# Ver_5.net
KiCad netlist of a schematic drawn in EAGLE
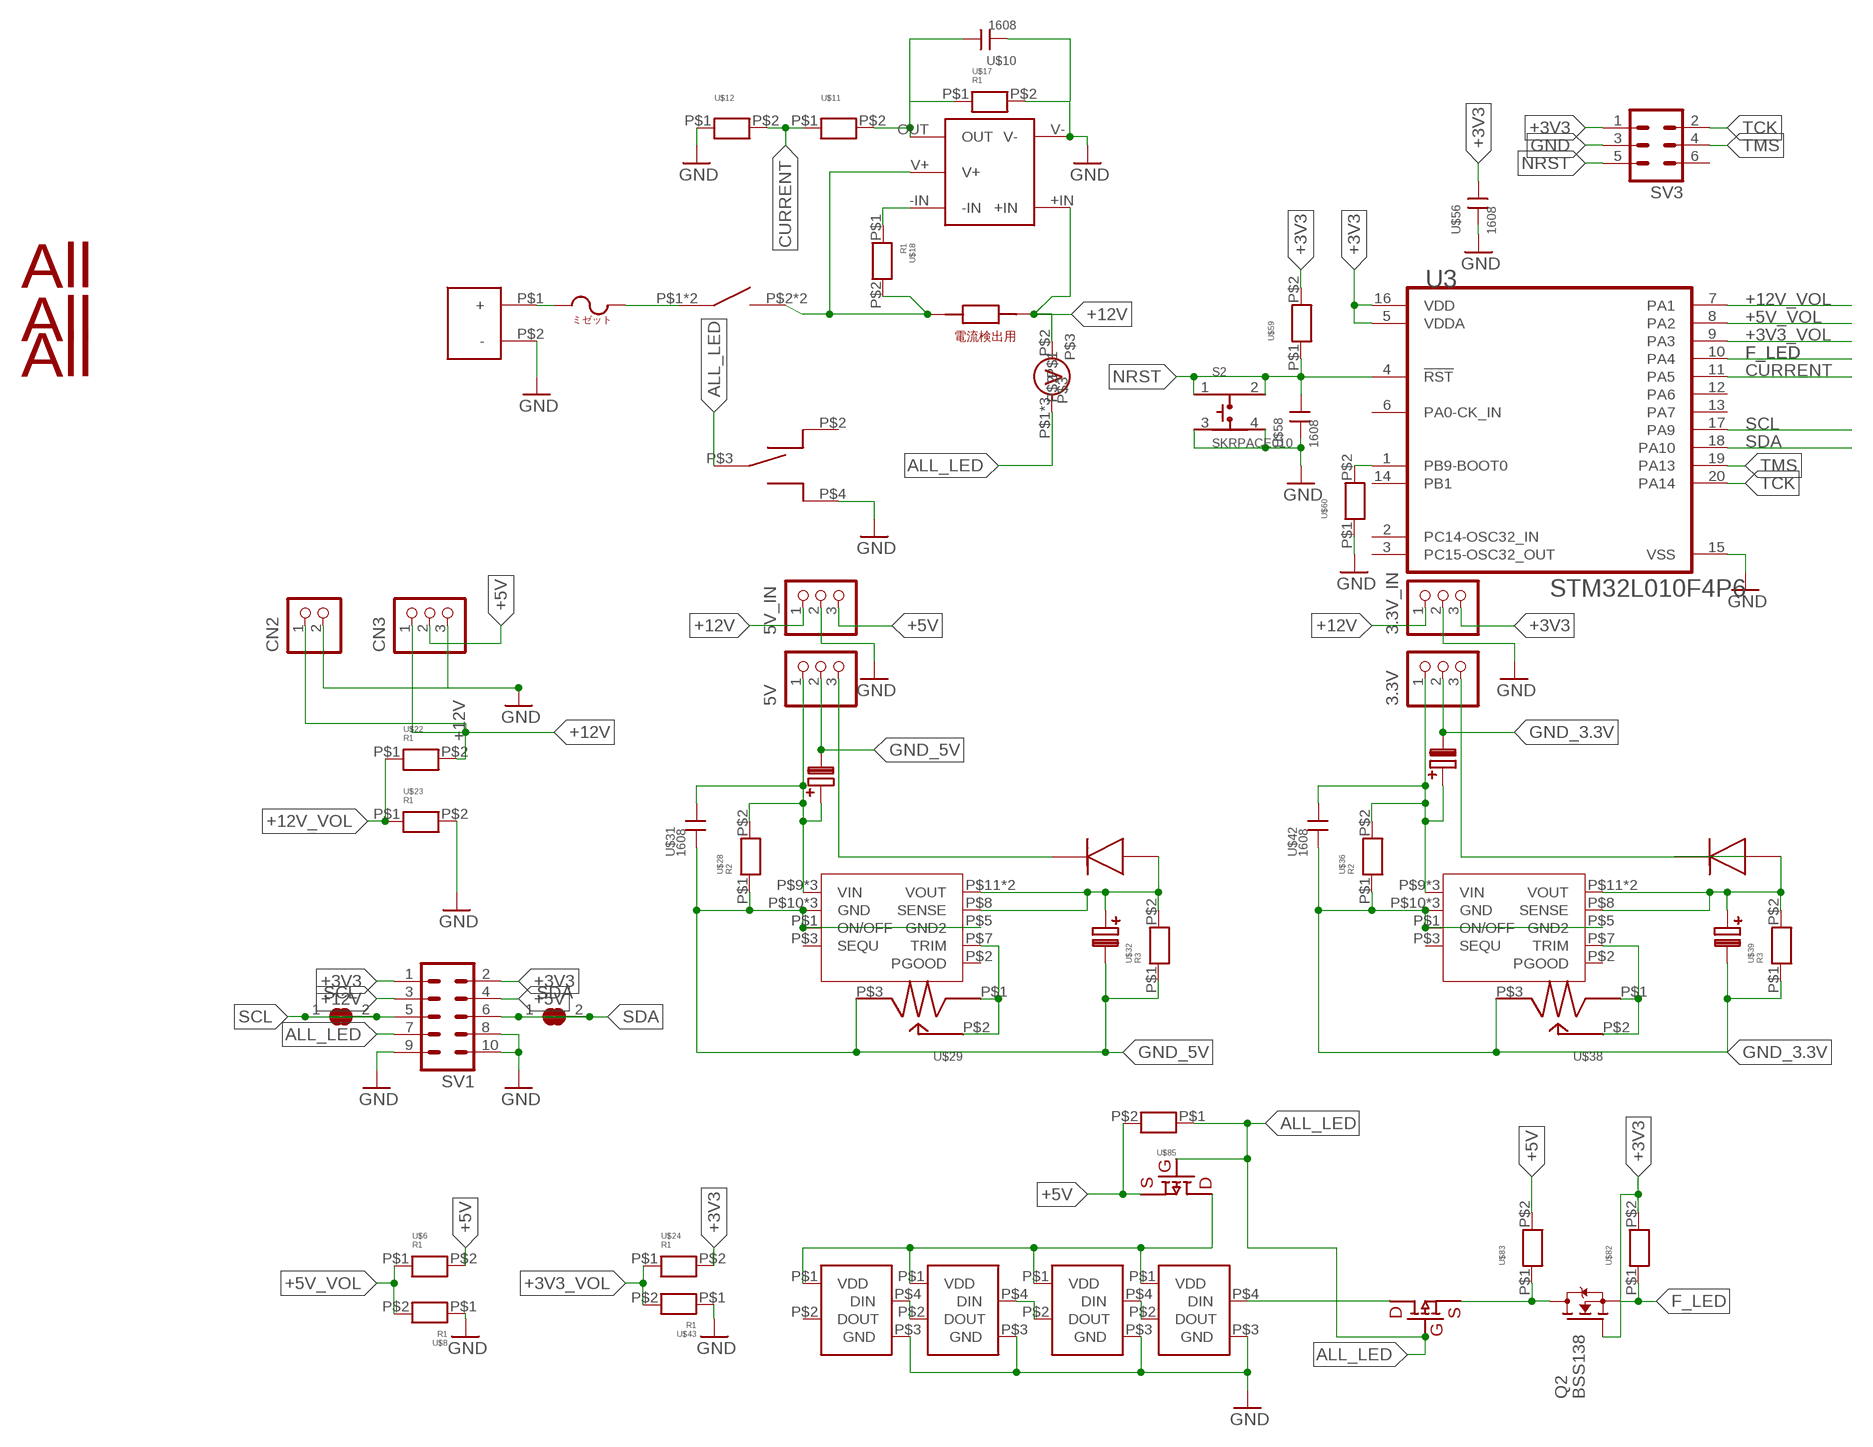
[diagram p0: schematic, sheet 1]

(export (version "E")
  (design (tool "Eeschema 10.0.6"))
  (components
    (comp (ref "3.3V")
      (value "B3B-XH-A")
      (footprint "eagle-import:B3B-XH-A")
      (libsource (lib "eagle-import") (part "B3B-XH-A"))
    )
    (comp (ref "3.3V_IN")
      (value "B3B-XH-A")
      (footprint "eagle-import:B3B-XH-A")
      (libsource (lib "eagle-import") (part "B3B-XH-A"))
    )
    (comp (ref "5V")
      (value "B3B-XH-A")
      (footprint "eagle-import:B3B-XH-A")
      (libsource (lib "eagle-import") (part "B3B-XH-A"))
    )
    (comp (ref "5V_IN")
      (value "B3B-XH-A")
      (footprint "eagle-import:B3B-XH-A")
      (libsource (lib "eagle-import") (part "B3B-XH-A"))
    )
    (comp (ref "CN2")
      (value "B2B-XH-A")
      (footprint "eagle-import:B2B-XH-A")
      (libsource (lib "eagle-import") (part "B2B-XH-A"))
    )
    (comp (ref "CN3")
      (value "B3B-XH-A")
      (footprint "eagle-import:B3B-XH-A")
      (libsource (lib "eagle-import") (part "B3B-XH-A"))
    )
    (comp (ref "F1")
      (value "LED")
      (footprint "eagle-import:LED")
      (libsource (lib "eagle-import") (part "LED"))
    )
    (comp (ref "F2")
      (value "LED")
      (footprint "eagle-import:LED")
      (libsource (lib "eagle-import") (part "LED"))
    )
    (comp (ref "F3")
      (value "LED")
      (footprint "eagle-import:LED")
      (libsource (lib "eagle-import") (part "LED"))
    )
    (comp (ref "F18")
      (value "LED")
      (footprint "eagle-import:LED")
      (libsource (lib "eagle-import") (part "LED"))
    )
    (comp (ref "Q2")
      (value "BSS138")
      (footprint "eagle-import:SOT23")
      (fields (field (name "MF") "Fairchild"))
      (libsource (lib "eagle-import") (part "BSS138"))
    )
    (comp (ref "S2")
      (value "SKRPACE010")
      (footprint "eagle-import:SW_SKRPACE010")
      (fields (field (name "MF") "ALPS"))
      (libsource (lib "eagle-import") (part "SKRPACE010"))
    )
    (comp (ref "SCL") (value "SJ") (footprint "eagle-import:SJ") (libsource (lib "eagle-import") (part "SJ")))
    (comp (ref "SDA") (value "SJ") (footprint "eagle-import:SJ") (libsource (lib "eagle-import") (part "SJ")))
    (comp (ref "SV1")
      (value "ML10")
      (footprint "eagle-import:ML10")
      (libsource (lib "eagle-import") (part "ML10"))
    )
    (comp (ref "SV3")
      (value "ML6")
      (footprint "eagle-import:ML6")
      (libsource (lib "eagle-import") (part "ML6"))
    )
    (comp (ref "U$1")
      (value "XT60")
      (footprint "eagle-import:XT60")
      (libsource (lib "eagle-import") (part "XT60"))
    )
    (comp (ref "U$2") (value "MF") (footprint "eagle-import:ｍｆ") (libsource (lib "eagle-import") (part "MF")))
    (comp (ref "U$3") (value "V") (footprint "eagle-import:V") (libsource (lib "eagle-import") (part "V")))
    (comp (ref "U$4")
      (value "SW3")
      (footprint "eagle-import:SW3")
      (libsource (lib "eagle-import") (part "SW3"))
    )
    (comp (ref "U$5")
      (value "25V100")
      (footprint "eagle-import:25V100")
      (libsource (lib "eagle-import") (part "25V100"))
    )
    (comp (ref "U$6")
      (value "R1")
      (footprint "eagle-import:1608")
      (libsource (lib "eagle-import") (part "R"))
    )
    (comp (ref "U$7")
      (value "25V100")
      (footprint "eagle-import:25V100")
      (libsource (lib "eagle-import") (part "25V100"))
    )
    (comp (ref "U$8")
      (value "R1")
      (footprint "eagle-import:1608")
      (libsource (lib "eagle-import") (part "R"))
    )
    (comp (ref "U$9")
      (value "ALL")
      (footprint "eagle-import:ALL")
      (libsource (lib "eagle-import") (part "ALL"))
    )
    (comp (ref "U$10")
      (value "1608")
      (footprint "eagle-import:CON")
      (libsource (lib "eagle-import") (part "1608"))
    )
    (comp (ref "U$11")
      (value "R")
      (footprint "eagle-import:1608")
      (libsource (lib "eagle-import") (part "R"))
    )
    (comp (ref "U$12")
      (value "R")
      (footprint "eagle-import:1608")
      (libsource (lib "eagle-import") (part "R"))
    )
    (comp (ref "U$13")
      (value "LT6106")
      (footprint "eagle-import:LT6106")
      (libsource (lib "eagle-import") (part "LT6106"))
    )
    (comp (ref "U$14")
      (value "R")
      (footprint "eagle-import:ｒ05")
      (libsource (lib "eagle-import") (part "R 1W0.1Ω_R"))
    )
    (comp (ref "U$15")
      (value "ALL")
      (footprint "eagle-import:ALL")
      (libsource (lib "eagle-import") (part "ALL"))
    )
    (comp (ref "U$16") (value "S") (footprint "eagle-import:S") (libsource (lib "eagle-import") (part "S")))
    (comp (ref "U$17")
      (value "R1")
      (footprint "eagle-import:1608")
      (libsource (lib "eagle-import") (part "R"))
    )
    (comp (ref "U$18")
      (value "R1")
      (footprint "eagle-import:1608")
      (libsource (lib "eagle-import") (part "R"))
    )
    (comp (ref "U$19")
      (value "ALL")
      (footprint "eagle-import:ALL")
      (libsource (lib "eagle-import") (part "ALL"))
    )
    (comp (ref "U$22")
      (value "R1")
      (footprint "eagle-import:1608")
      (libsource (lib "eagle-import") (part "R"))
    )
    (comp (ref "U$23")
      (value "R1")
      (footprint "eagle-import:1608")
      (libsource (lib "eagle-import") (part "R"))
    )
    (comp (ref "U$24")
      (value "R1")
      (footprint "eagle-import:1608")
      (libsource (lib "eagle-import") (part "R"))
    )
    (comp (ref "U$26")
      (value "DCDC")
      (footprint "eagle-import:DC-DC")
      (libsource (lib "eagle-import") (part "DCDC"))
    )
    (comp (ref "U$28")
      (value "R2")
      (footprint "eagle-import:1608")
      (libsource (lib "eagle-import") (part "R"))
    )
    (comp (ref "U$29")
      (value "VR")
      (footprint "eagle-import:VR")
      (libsource (lib "eagle-import") (part "VR"))
    )
    (comp (ref "U$30")
      (value "25V100")
      (footprint "eagle-import:25V100")
      (libsource (lib "eagle-import") (part "25V100"))
    )
    (comp (ref "U$31")
      (value "1608")
      (footprint "eagle-import:CON")
      (libsource (lib "eagle-import") (part "1608"))
    )
    (comp (ref "U$32")
      (value "R3")
      (footprint "eagle-import:1608")
      (libsource (lib "eagle-import") (part "R"))
    )
    (comp (ref "U$33")
      (value "40V5A")
      (footprint "eagle-import:40V5A")
      (libsource (lib "eagle-import") (part "40V5A"))
    )
    (comp (ref "U$34")
      (value "DCDC")
      (footprint "eagle-import:DC-DC")
      (libsource (lib "eagle-import") (part "DCDC"))
    )
    (comp (ref "U$36")
      (value "R2")
      (footprint "eagle-import:1608")
      (libsource (lib "eagle-import") (part "R"))
    )
    (comp (ref "U$37")
      (value "40V5A")
      (footprint "eagle-import:40V5A")
      (libsource (lib "eagle-import") (part "40V5A"))
    )
    (comp (ref "U$38")
      (value "VR")
      (footprint "eagle-import:VR")
      (libsource (lib "eagle-import") (part "VR"))
    )
    (comp (ref "U$39")
      (value "R3")
      (footprint "eagle-import:1608")
      (libsource (lib "eagle-import") (part "R"))
    )
    (comp (ref "U$40")
      (value "25V100")
      (footprint "eagle-import:25V100")
      (libsource (lib "eagle-import") (part "25V100"))
    )
    (comp (ref "U$42")
      (value "1608")
      (footprint "eagle-import:CON")
      (libsource (lib "eagle-import") (part "1608"))
    )
    (comp (ref "U$43")
      (value "R1")
      (footprint "eagle-import:1608")
      (libsource (lib "eagle-import") (part "R"))
    )
    (comp (ref "U$56")
      (value "1608")
      (footprint "eagle-import:CON")
      (libsource (lib "eagle-import") (part "1608"))
    )
    (comp (ref "U$58")
      (value "1608")
      (footprint "eagle-import:CON")
      (libsource (lib "eagle-import") (part "1608"))
    )
    (comp (ref "U$59")
      (value "R")
      (footprint "eagle-import:1608")
      (libsource (lib "eagle-import") (part "R"))
    )
    (comp (ref "U$60")
      (value "R")
      (footprint "eagle-import:1608")
      (libsource (lib "eagle-import") (part "R"))
    )
    (comp (ref "U$82")
      (value "R")
      (footprint "eagle-import:1608")
      (libsource (lib "eagle-import") (part "R"))
    )
    (comp (ref "U$83")
      (value "R")
      (footprint "eagle-import:1608")
      (libsource (lib "eagle-import") (part "R"))
    )
    (comp (ref "U$84")
      (value "808")
      (footprint "eagle-import:808")
      (libsource (lib "eagle-import") (part "808"))
    )
    (comp (ref "U$85")
      (value "R")
      (footprint "eagle-import:1608")
      (libsource (lib "eagle-import") (part "R"))
    )
    (comp (ref "U$86")
      (value "808")
      (footprint "eagle-import:808")
      (libsource (lib "eagle-import") (part "808"))
    )
    (comp (ref "U3")
      (value "STMICROELECTRONICS_STM32L010F4P6STMICROELECTRONICS_STM32L010F4P6_0_0")
      (footprint "eagle-import:STMICROELECTRONICS_STM32L010F4P6_0")
      (fields
        (field (name "DIGIKEY_PART_NUMBER") "497-19364-ND")
        (field (name "MF") "STMicroelectronics")
        (field (name "MOUSER_PART_NUMBER") "511-STM32L010F4P6")
      )
      (libsource (lib "eagle-import") (part "STMICROELECTRONICS_STM32L010F4P6STMICROELECTRONICS_STM32L010F4P6_0_0"))
    )
  )
  (nets
    (net (code "1") (name "+3V3") (class "Default")
      (node (ref "3.3V_IN") (pin "3") (pinfunction "3_3") (pintype "passive"))
      (node (ref "Q2") (pin "1") (pinfunction "G_1") (pintype "passive"))
      (node (ref "SV1") (pin "1") (pinfunction "1_1") (pintype "passive"))
      (node (ref "SV1") (pin "2") (pinfunction "2_2") (pintype "passive"))
      (node (ref "SV3") (pin "1") (pinfunction "1_1") (pintype "passive"))
      (node (ref "U$24") (pin "P$2") (pinfunction "P$2_P$2") (pintype "bidirectional"))
      (node (ref "U$56") (pin "P$1") (pinfunction "1_P$1") (pintype "bidirectional"))
      (node (ref "U$59") (pin "P$2") (pinfunction "P$2_P$2") (pintype "bidirectional"))
      (node (ref "U$82") (pin "P$2") (pinfunction "P$2_P$2") (pintype "bidirectional"))
      (node (ref "U3") (pin "16") (pinfunction "VDD_16") (pintype "power_in"))
      (node (ref "U3") (pin "5") (pinfunction "VDDA_5") (pintype "power_in"))
    )
    (net (code "2") (name "+3V3_VOL") (class "Default")
      (node (ref "U$24") (pin "P$1") (pinfunction "P$1_P$1") (pintype "bidirectional"))
      (node (ref "U$43") (pin "P$2") (pinfunction "P$2_P$2") (pintype "bidirectional"))
      (node (ref "U3") (pin "9") (pinfunction "PA3_9") (pintype "bidirectional"))
    )
    (net (code "3") (name "+5V") (class "Default")
      (node (ref "5V_IN") (pin "3") (pinfunction "3_3") (pintype "passive"))
      (node (ref "CN3") (pin "2") (pinfunction "2_2") (pintype "passive"))
      (node (ref "SV1") (pin "4") (pinfunction "4_4") (pintype "passive"))
      (node (ref "U$6") (pin "P$2") (pinfunction "P$2_P$2") (pintype "bidirectional"))
      (node (ref "U$83") (pin "P$2") (pinfunction "P$2_P$2") (pintype "bidirectional"))
      (node (ref "U$84") (pin "S") (pinfunction "S_S") (pintype "bidirectional"))
      (node (ref "U$85") (pin "P$2") (pinfunction "P$2_P$2") (pintype "bidirectional"))
    )
    (net (code "4") (name "+5V_VOL") (class "Default")
      (node (ref "U$6") (pin "P$1") (pinfunction "P$1_P$1") (pintype "bidirectional"))
      (node (ref "U$8") (pin "P$2") (pinfunction "P$2_P$2") (pintype "bidirectional"))
      (node (ref "U3") (pin "8") (pinfunction "PA2_8") (pintype "bidirectional"))
    )
    (net (code "5") (name "+12V") (class "Default")
      (node (ref "3.3V_IN") (pin "1") (pinfunction "1_1") (pintype "passive"))
      (node (ref "5V_IN") (pin "1") (pinfunction "1_1") (pintype "passive"))
      (node (ref "CN2") (pin "1") (pinfunction "1_1") (pintype "passive"))
      (node (ref "CN3") (pin "1") (pinfunction "1_1") (pintype "passive"))
      (node (ref "SV1") (pin "3") (pinfunction "3_3") (pintype "passive"))
      (node (ref "U$13") (pin "+IN") (pinfunction "+IN_+IN") (pintype "bidirectional"))
      (node (ref "U$14") (pin "P$1") (pinfunction "P$1_P$1") (pintype "bidirectional"))
      (node (ref "U$22") (pin "P$2") (pinfunction "P$2_P$2") (pintype "bidirectional"))
      (node (ref "U$3") (pin "P$2") (pinfunction "P$2_P$2") (pintype "bidirectional"))
    )
    (net (code "6") (name "+12V_VOL") (class "Default")
      (node (ref "U$22") (pin "P$1") (pinfunction "P$1_P$1") (pintype "bidirectional"))
      (node (ref "U$23") (pin "P$1") (pinfunction "P$1_P$1") (pintype "bidirectional"))
      (node (ref "U3") (pin "7") (pinfunction "PA1_7") (pintype "bidirectional"))
    )
    (net (code "7") (name "ALL_LED") (class "Default")
      (node (ref "SV1") (pin "7") (pinfunction "7_7") (pintype "passive"))
      (node (ref "U$16") (pin "P$3") (pinfunction "2_P$3") (pintype "bidirectional"))
      (node (ref "U$3") (pin "P$1") (pinfunction "P$1_P$1") (pintype "bidirectional"))
      (node (ref "U$3") (pin "P$4") (pinfunction "P$1_P$4") (pintype "bidirectional"))
      (node (ref "U$3") (pin "P$5") (pinfunction "P$1_P$5") (pintype "bidirectional"))
      (node (ref "U$84") (pin "G") (pinfunction "G_G") (pintype "bidirectional"))
      (node (ref "U$85") (pin "P$1") (pinfunction "P$1_P$1") (pintype "bidirectional"))
      (node (ref "U$86") (pin "G") (pinfunction "G_G") (pintype "bidirectional"))
    )
    (net (code "8") (name "CURRENT") (class "Default")
      (node (ref "U$11") (pin "P$1") (pinfunction "P$1_P$1") (pintype "bidirectional"))
      (node (ref "U$12") (pin "P$2") (pinfunction "P$2_P$2") (pintype "bidirectional"))
      (node (ref "U3") (pin "11") (pinfunction "PA5_11") (pintype "bidirectional"))
    )
    (net (code "9") (name "F_LED") (class "Default")
      (node (ref "Q2") (pin "2") (pinfunction "S_2") (pintype "passive"))
      (node (ref "U$82") (pin "P$1") (pinfunction "P$1_P$1") (pintype "bidirectional"))
      (node (ref "U3") (pin "10") (pinfunction "PA4_10") (pintype "bidirectional"))
    )
    (net (code "10") (name "GND") (class "Default")
      (node (ref "3.3V_IN") (pin "2") (pinfunction "2_2") (pintype "passive"))
      (node (ref "5V_IN") (pin "2") (pinfunction "2_2") (pintype "passive"))
      (node (ref "CN2") (pin "2") (pinfunction "2_2") (pintype "passive"))
      (node (ref "CN3") (pin "3") (pinfunction "3_3") (pintype "passive"))
      (node (ref "F1") (pin "P$3") (pinfunction "GND_P$3") (pintype "bidirectional"))
      (node (ref "F18") (pin "P$3") (pinfunction "GND_P$3") (pintype "bidirectional"))
      (node (ref "F2") (pin "P$3") (pinfunction "GND_P$3") (pintype "bidirectional"))
      (node (ref "F3") (pin "P$3") (pinfunction "GND_P$3") (pintype "bidirectional"))
      (node (ref "S2") (pin "3") (pinfunction "3_3") (pintype "bidirectional"))
      (node (ref "S2") (pin "4") (pinfunction "4_4") (pintype "bidirectional"))
      (node (ref "SV1") (pin "10") (pinfunction "10_10") (pintype "passive"))
      (node (ref "SV1") (pin "8") (pinfunction "8_8") (pintype "passive"))
      (node (ref "SV1") (pin "9") (pinfunction "9_9") (pintype "passive"))
      (node (ref "SV3") (pin "3") (pinfunction "3_3") (pintype "passive"))
      (node (ref "U$1") (pin "P$2") (pinfunction "-_P$2") (pintype "bidirectional"))
      (node (ref "U$10") (pin "P$2") (pinfunction "2_P$2") (pintype "bidirectional"))
      (node (ref "U$12") (pin "P$1") (pinfunction "P$1_P$1") (pintype "bidirectional"))
      (node (ref "U$13") (pin "V-") (pinfunction "V-_V-") (pintype "bidirectional"))
      (node (ref "U$16") (pin "P$4") (pinfunction "3_P$4") (pintype "bidirectional"))
      (node (ref "U$17") (pin "P$2") (pinfunction "P$2_P$2") (pintype "bidirectional"))
      (node (ref "U$23") (pin "P$2") (pinfunction "P$2_P$2") (pintype "bidirectional"))
      (node (ref "U$43") (pin "P$1") (pinfunction "P$1_P$1") (pintype "bidirectional"))
      (node (ref "U$56") (pin "P$2") (pinfunction "2_P$2") (pintype "bidirectional"))
      (node (ref "U$58") (pin "P$2") (pinfunction "2_P$2") (pintype "bidirectional"))
      (node (ref "U$60") (pin "P$1") (pinfunction "P$1_P$1") (pintype "bidirectional"))
      (node (ref "U$8") (pin "P$1") (pinfunction "P$1_P$1") (pintype "bidirectional"))
      (node (ref "U3") (pin "15") (pinfunction "VSS_15") (pintype "power_in"))
    )
    (net (code "11") (name "GND_3.3V") (class "Default")
      (node (ref "3.3V") (pin "2") (pinfunction "2_2") (pintype "passive"))
      (node (ref "U$34") (pin "P$1") (pinfunction "ON/OFF_P$1") (pintype "bidirectional"))
      (node (ref "U$34") (pin "P$10") (pinfunction "GND_P$10") (pintype "bidirectional"))
      (node (ref "U$34") (pin "P$16") (pinfunction "GND_P$16") (pintype "bidirectional"))
      (node (ref "U$34") (pin "P$17") (pinfunction "GND_P$17") (pintype "bidirectional"))
      (node (ref "U$34") (pin "P$5") (pinfunction "GND2_P$5") (pintype "bidirectional"))
      (node (ref "U$36") (pin "P$1") (pinfunction "P$1_P$1") (pintype "bidirectional"))
      (node (ref "U$38") (pin "P$3") (pinfunction "P$3_P$3") (pintype "bidirectional"))
      (node (ref "U$39") (pin "P$1") (pinfunction "P$1_P$1") (pintype "bidirectional"))
      (node (ref "U$40") (pin "P$2") (pinfunction "P$2_P$2") (pintype "bidirectional"))
      (node (ref "U$42") (pin "P$2") (pinfunction "2_P$2") (pintype "bidirectional"))
      (node (ref "U$7") (pin "P$2") (pinfunction "P$2_P$2") (pintype "bidirectional"))
    )
    (net (code "12") (name "GND_5V") (class "Default")
      (node (ref "5V") (pin "2") (pinfunction "2_2") (pintype "passive"))
      (node (ref "U$26") (pin "P$1") (pinfunction "ON/OFF_P$1") (pintype "bidirectional"))
      (node (ref "U$26") (pin "P$10") (pinfunction "GND_P$10") (pintype "bidirectional"))
      (node (ref "U$26") (pin "P$16") (pinfunction "GND_P$16") (pintype "bidirectional"))
      (node (ref "U$26") (pin "P$17") (pinfunction "GND_P$17") (pintype "bidirectional"))
      (node (ref "U$26") (pin "P$5") (pinfunction "GND2_P$5") (pintype "bidirectional"))
      (node (ref "U$28") (pin "P$1") (pinfunction "P$1_P$1") (pintype "bidirectional"))
      (node (ref "U$29") (pin "P$3") (pinfunction "P$3_P$3") (pintype "bidirectional"))
      (node (ref "U$30") (pin "P$2") (pinfunction "P$2_P$2") (pintype "bidirectional"))
      (node (ref "U$31") (pin "P$2") (pinfunction "2_P$2") (pintype "bidirectional"))
      (node (ref "U$32") (pin "P$1") (pinfunction "P$1_P$1") (pintype "bidirectional"))
      (node (ref "U$5") (pin "P$2") (pinfunction "P$2_P$2") (pintype "bidirectional"))
    )
    (net (code "13") (name "NRST") (class "Default")
      (node (ref "S2") (pin "1") (pinfunction "1_1") (pintype "bidirectional"))
      (node (ref "S2") (pin "2") (pinfunction "2_2") (pintype "bidirectional"))
      (node (ref "SV3") (pin "5") (pinfunction "5_5") (pintype "passive"))
      (node (ref "U$58") (pin "P$1") (pinfunction "1_P$1") (pintype "bidirectional"))
      (node (ref "U$59") (pin "P$1") (pinfunction "P$1_P$1") (pintype "bidirectional"))
      (node (ref "U3") (pin "4") (pinfunction "~{RST}_4") (pintype "input"))
    )
    (net (code "14") (name "Net-(3.3V-Pad3)") (class "Default")
      (node (ref "3.3V") (pin "3") (pinfunction "3_3") (pintype "passive"))
      (node (ref "U$37") (pin "P$2") (pinfunction "P$2_P$2") (pintype "bidirectional"))
    )
    (net (code "15") (name "Net-(5V-Pad3)") (class "Default")
      (node (ref "5V") (pin "3") (pinfunction "3_3") (pintype "passive"))
      (node (ref "U$33") (pin "P$2") (pinfunction "P$2_P$2") (pintype "bidirectional"))
    )
    (net (code "16") (name "Net-(F1-DIN)") (class "Default")
      (node (ref "F1") (pin "P$4") (pinfunction "DIN_P$4") (pintype "bidirectional"))
      (node (ref "F18") (pin "P$2") (pinfunction "DOUT_P$2") (pintype "bidirectional"))
    )
    (net (code "17") (name "Net-(F1-DOUT)") (class "Default")
      (node (ref "F1") (pin "P$2") (pinfunction "DOUT_P$2") (pintype "bidirectional"))
      (node (ref "F2") (pin "P$4") (pinfunction "DIN_P$4") (pintype "bidirectional"))
    )
    (net (code "18") (name "Net-(F1-VDD)") (class "Default")
      (node (ref "F1") (pin "P$1") (pinfunction "VDD_P$1") (pintype "bidirectional"))
      (node (ref "F18") (pin "P$1") (pinfunction "VDD_P$1") (pintype "bidirectional"))
      (node (ref "F2") (pin "P$1") (pinfunction "VDD_P$1") (pintype "bidirectional"))
      (node (ref "F3") (pin "P$1") (pinfunction "VDD_P$1") (pintype "bidirectional"))
      (node (ref "U$84") (pin "D") (pinfunction "D_D") (pintype "bidirectional"))
      (node (ref "U$84") (pin "DD") (pinfunction "D_DD") (pintype "bidirectional"))
      (node (ref "U$84") (pin "DDD") (pinfunction "D_DDD") (pintype "bidirectional"))
      (node (ref "U$84") (pin "DDDD") (pinfunction "D_DDDD") (pintype "bidirectional"))
    )
    (net (code "19") (name "Net-(F2-DOUT)") (class "Default")
      (node (ref "F2") (pin "P$2") (pinfunction "DOUT_P$2") (pintype "bidirectional"))
      (node (ref "F3") (pin "P$4") (pinfunction "DIN_P$4") (pintype "bidirectional"))
    )
    (net (code "20") (name "Net-(F18-DIN)") (class "Default")
      (node (ref "F18") (pin "P$4") (pinfunction "DIN_P$4") (pintype "bidirectional"))
      (node (ref "U$86") (pin "D") (pinfunction "D_D") (pintype "bidirectional"))
      (node (ref "U$86") (pin "DD") (pinfunction "D_DD") (pintype "bidirectional"))
      (node (ref "U$86") (pin "DDD") (pinfunction "D_DDD") (pintype "bidirectional"))
      (node (ref "U$86") (pin "DDDD") (pinfunction "D_DDDD") (pintype "bidirectional"))
    )
    (net (code "21") (name "Net-(Q2-D)") (class "Default")
      (node (ref "Q2") (pin "3") (pinfunction "D_3") (pintype "passive"))
      (node (ref "U$83") (pin "P$1") (pinfunction "P$1_P$1") (pintype "bidirectional"))
      (node (ref "U$86") (pin "S") (pinfunction "S_S") (pintype "bidirectional"))
    )
    (net (code "22") (name "Net-(U$1-+)") (class "Default")
      (node (ref "U$1") (pin "P$1") (pinfunction "+_P$1") (pintype "bidirectional"))
      (node (ref "U$2") (pin "P$1") (pinfunction "P$1_P$1") (pintype "bidirectional"))
      (node (ref "U$2") (pin "P$2") (pinfunction "P$1_P$2") (pintype "bidirectional"))
    )
    (net (code "23") (name "Net-(U$2-P$2-PadP$3)") (class "Default")
      (node (ref "U$2") (pin "P$3") (pinfunction "P$2_P$3") (pintype "bidirectional"))
      (node (ref "U$2") (pin "P$4") (pinfunction "P$2_P$4") (pintype "bidirectional"))
      (node (ref "U$4") (pin "P$1") (pinfunction "P$1_P$1") (pintype "bidirectional"))
      (node (ref "U$4") (pin "P$3") (pinfunction "P$1_P$3") (pintype "bidirectional"))
    )
    (net (code "24") (name "Net-(U$10-1)") (class "Default")
      (node (ref "U$10") (pin "P$1") (pinfunction "1_P$1") (pintype "bidirectional"))
      (node (ref "U$11") (pin "P$2") (pinfunction "P$2_P$2") (pintype "bidirectional"))
      (node (ref "U$13") (pin "OUT") (pinfunction "OUT_OUT") (pintype "bidirectional"))
      (node (ref "U$17") (pin "P$1") (pinfunction "P$1_P$1") (pintype "bidirectional"))
    )
    (net (code "25") (name "Net-(U$13-Pad-IN)") (class "Default")
      (node (ref "U$13") (pin "-IN") (pinfunction "-IN_-IN") (pintype "bidirectional"))
      (node (ref "U$18") (pin "P$1") (pinfunction "P$1_P$1") (pintype "bidirectional"))
    )
    (net (code "26") (name "Net-(U$13-PadV+)") (class "Default")
      (node (ref "U$13") (pin "V+") (pinfunction "V+_V+") (pintype "bidirectional"))
      (node (ref "U$14") (pin "P$2") (pinfunction "P$2_P$2") (pintype "bidirectional"))
      (node (ref "U$18") (pin "P$2") (pinfunction "P$2_P$2") (pintype "bidirectional"))
      (node (ref "U$4") (pin "P$2") (pinfunction "P$2_P$2") (pintype "bidirectional"))
      (node (ref "U$4") (pin "P$4") (pinfunction "P$2_P$4") (pintype "bidirectional"))
    )
    (net (code "27") (name "Net-(U$26-SENSE)") (class "Default")
      (node (ref "U$26") (pin "P$11") (pinfunction "VOUT_P$11") (pintype "bidirectional"))
      (node (ref "U$26") (pin "P$18") (pinfunction "VOUT_P$18") (pintype "bidirectional"))
      (node (ref "U$26") (pin "P$8") (pinfunction "SENSE_P$8") (pintype "bidirectional"))
      (node (ref "U$30") (pin "P$1") (pinfunction "P$1_P$1") (pintype "bidirectional"))
      (node (ref "U$32") (pin "P$2") (pinfunction "P$2_P$2") (pintype "bidirectional"))
      (node (ref "U$33") (pin "P$1") (pinfunction "P$1_P$1") (pintype "bidirectional"))
    )
    (net (code "28") (name "Net-(U$26-TRIM)") (class "Default")
      (node (ref "U$26") (pin "P$7") (pinfunction "TRIM_P$7") (pintype "bidirectional"))
      (node (ref "U$29") (pin "P$1") (pinfunction "P$1_P$1") (pintype "bidirectional"))
      (node (ref "U$29") (pin "P$2") (pinfunction "P$2_P$2") (pintype "bidirectional"))
    )
    (net (code "29") (name "Net-(U$31-1)") (class "Default")
      (node (ref "5V") (pin "1") (pinfunction "1_1") (pintype "passive"))
      (node (ref "U$26") (pin "P$14") (pinfunction "VIN_P$14") (pintype "bidirectional"))
      (node (ref "U$26") (pin "P$15") (pinfunction "VIN_P$15") (pintype "bidirectional"))
      (node (ref "U$26") (pin "P$9") (pinfunction "VIN_P$9") (pintype "bidirectional"))
      (node (ref "U$28") (pin "P$2") (pinfunction "P$2_P$2") (pintype "bidirectional"))
      (node (ref "U$31") (pin "P$1") (pinfunction "1_P$1") (pintype "bidirectional"))
      (node (ref "U$5") (pin "P$1") (pinfunction "P$1_P$1") (pintype "bidirectional"))
    )
    (net (code "30") (name "Net-(U$34-SENSE)") (class "Default")
      (node (ref "U$34") (pin "P$11") (pinfunction "VOUT_P$11") (pintype "bidirectional"))
      (node (ref "U$34") (pin "P$18") (pinfunction "VOUT_P$18") (pintype "bidirectional"))
      (node (ref "U$34") (pin "P$8") (pinfunction "SENSE_P$8") (pintype "bidirectional"))
      (node (ref "U$37") (pin "P$1") (pinfunction "P$1_P$1") (pintype "bidirectional"))
      (node (ref "U$39") (pin "P$2") (pinfunction "P$2_P$2") (pintype "bidirectional"))
      (node (ref "U$40") (pin "P$1") (pinfunction "P$1_P$1") (pintype "bidirectional"))
    )
    (net (code "31") (name "Net-(U$34-TRIM)") (class "Default")
      (node (ref "U$34") (pin "P$7") (pinfunction "TRIM_P$7") (pintype "bidirectional"))
      (node (ref "U$38") (pin "P$1") (pinfunction "P$1_P$1") (pintype "bidirectional"))
      (node (ref "U$38") (pin "P$2") (pinfunction "P$2_P$2") (pintype "bidirectional"))
    )
    (net (code "32") (name "Net-(U$42-1)") (class "Default")
      (node (ref "3.3V") (pin "1") (pinfunction "1_1") (pintype "passive"))
      (node (ref "U$34") (pin "P$14") (pinfunction "VIN_P$14") (pintype "bidirectional"))
      (node (ref "U$34") (pin "P$15") (pinfunction "VIN_P$15") (pintype "bidirectional"))
      (node (ref "U$34") (pin "P$9") (pinfunction "VIN_P$9") (pintype "bidirectional"))
      (node (ref "U$36") (pin "P$2") (pinfunction "P$2_P$2") (pintype "bidirectional"))
      (node (ref "U$42") (pin "P$1") (pinfunction "1_P$1") (pintype "bidirectional"))
      (node (ref "U$7") (pin "P$1") (pinfunction "P$1_P$1") (pintype "bidirectional"))
    )
    (net (code "33") (name "Net-(U3-PB9-BOOT0)") (class "Default")
      (node (ref "U$60") (pin "P$2") (pinfunction "P$2_P$2") (pintype "bidirectional"))
      (node (ref "U3") (pin "1") (pinfunction "PB9-BOOT0_1") (pintype "input"))
    )
    (net (code "34") (name "SCL") (class "Default")
      (node (ref "SCL") (pin "1") (pinfunction "1_1") (pintype "passive"))
      (node (ref "SCL") (pin "2") (pinfunction "2_2") (pintype "passive"))
      (node (ref "SV1") (pin "5") (pinfunction "5_5") (pintype "passive"))
      (node (ref "U3") (pin "17") (pinfunction "PA9_17") (pintype "bidirectional"))
    )
    (net (code "35") (name "SDA") (class "Default")
      (node (ref "SDA") (pin "1") (pinfunction "1_1") (pintype "passive"))
      (node (ref "SDA") (pin "2") (pinfunction "2_2") (pintype "passive"))
      (node (ref "SV1") (pin "6") (pinfunction "6_6") (pintype "passive"))
      (node (ref "U3") (pin "18") (pinfunction "PA10_18") (pintype "bidirectional"))
    )
    (net (code "36") (name "TCK") (class "Default")
      (node (ref "SV3") (pin "2") (pinfunction "2_2") (pintype "passive"))
      (node (ref "U3") (pin "20") (pinfunction "PA14_20") (pintype "bidirectional"))
    )
    (net (code "37") (name "TMS") (class "Default")
      (node (ref "SV3") (pin "4") (pinfunction "4_4") (pintype "passive"))
      (node (ref "U3") (pin "19") (pinfunction "PA13_19") (pintype "bidirectional"))
    )
    (net (code "38") (name "unconnected-(F3-DOUT-PadP$2)") (class "Default")
      (node (ref "F3") (pin "P$2") (pinfunction "DOUT_P$2") (pintype "bidirectional"))
    )
    (net (code "39") (name "unconnected-(SV3-Pad6)") (class "Default")
      (node (ref "SV3") (pin "6") (pinfunction "6_6") (pintype "passive"))
    )
    (net (code "40") (name "unconnected-(U$3-PadP$3)") (class "Default")
      (node (ref "U$3") (pin "P$3") (pinfunction "P$3_P$3") (pintype "bidirectional"))
    )
    (net (code "41") (name "unconnected-(U$16-1-PadP$2)") (class "Default")
      (node (ref "U$16") (pin "P$2") (pinfunction "1_P$2") (pintype "bidirectional"))
    )
    (net (code "42") (name "unconnected-(U$26-PGOOD-PadP$2)") (class "Default")
      (node (ref "U$26") (pin "P$2") (pinfunction "PGOOD_P$2") (pintype "bidirectional"))
    )
    (net (code "43") (name "unconnected-(U$26-SEQU-PadP$3)") (class "Default")
      (node (ref "U$26") (pin "P$3") (pinfunction "SEQU_P$3") (pintype "bidirectional"))
    )
    (net (code "44") (name "unconnected-(U$34-PGOOD-PadP$2)") (class "Default")
      (node (ref "U$34") (pin "P$2") (pinfunction "PGOOD_P$2") (pintype "bidirectional"))
    )
    (net (code "45") (name "unconnected-(U$34-SEQU-PadP$3)") (class "Default")
      (node (ref "U$34") (pin "P$3") (pinfunction "SEQU_P$3") (pintype "bidirectional"))
    )
    (net (code "46") (name "unconnected-(U3-PA0-CK_IN-Pad6)") (class "Default")
      (node (ref "U3") (pin "6") (pinfunction "PA0-CK_IN_6") (pintype "bidirectional"))
    )
    (net (code "47") (name "unconnected-(U3-PA6-Pad12)") (class "Default")
      (node (ref "U3") (pin "12") (pinfunction "PA6_12") (pintype "bidirectional"))
    )
    (net (code "48") (name "unconnected-(U3-PA7-Pad13)") (class "Default")
      (node (ref "U3") (pin "13") (pinfunction "PA7_13") (pintype "bidirectional"))
    )
    (net (code "49") (name "unconnected-(U3-PB1-Pad14)") (class "Default")
      (node (ref "U3") (pin "14") (pinfunction "PB1_14") (pintype "bidirectional"))
    )
    (net (code "50") (name "unconnected-(U3-PC14-OSC32_IN-Pad2)") (class "Default")
      (node (ref "U3") (pin "2") (pinfunction "PC14-OSC32_IN_2") (pintype "bidirectional"))
    )
    (net (code "51") (name "unconnected-(U3-PC15-OSC32_OUT-Pad3)") (class "Default")
      (node (ref "U3") (pin "3") (pinfunction "PC15-OSC32_OUT_3") (pintype "bidirectional"))
    )
  )
)
